# Tesla.net
KiCad netlist of a schematic drawn in EAGLE
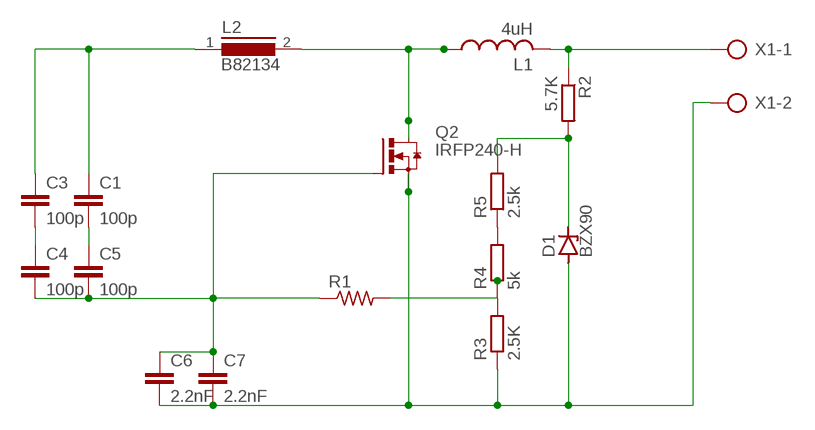
[diagram p0: schematic, sheet 1]

(export (version "E")
  (design (tool "Eeschema 10.0.6"))
  (components
    (comp (ref "C1")
      (value "100p")
      (footprint "eagle-import:C15B5")
      (libsource (lib "eagle-import") (part "C15/5"))
    )
    (comp (ref "C3")
      (value "100p")
      (footprint "eagle-import:C15B5")
      (libsource (lib "eagle-import") (part "C15/5"))
    )
    (comp (ref "C4")
      (value "100p")
      (footprint "eagle-import:C15B5")
      (libsource (lib "eagle-import") (part "C15/5"))
    )
    (comp (ref "C5")
      (value "100p")
      (footprint "eagle-import:C15B5")
      (libsource (lib "eagle-import") (part "C15/5"))
    )
    (comp (ref "C6")
      (value "2.2nF")
      (footprint "eagle-import:C15B5")
      (libsource (lib "eagle-import") (part "C15/5"))
    )
    (comp (ref "C7")
      (value "2.2nF")
      (footprint "eagle-import:C15B5")
      (libsource (lib "eagle-import") (part "C15/5"))
    )
    (comp (ref "D1")
      (value "BZX90")
      (footprint "eagle-import:DO34Z7")
      (libsource (lib "eagle-import") (part "BZX90"))
    )
    (comp (ref "L1")
      (value "4uH")
      (footprint "eagle-import:TFI0510")
      (libsource (lib "eagle-import") (part "L-USTFI0510"))
    )
    (comp (ref "L2")
      (value "B82134")
      (footprint "eagle-import:SUKW4-32")
      (libsource (lib "eagle-import") (part "B82134"))
    )
    (comp (ref "Q2")
      (value "IRFP240-H")
      (footprint "eagle-import:TO247BH")
      (libsource (lib "eagle-import") (part "IRFP240-H"))
    )
    (comp (ref "R1")
      (value "R-US_0309/12")
      (footprint "eagle-import:0309_12")
      (libsource (lib "eagle-import") (part "R-US_0309/12"))
    )
    (comp (ref "R2")
      (value "5.7K")
      (footprint "eagle-import:0204_7")
      (libsource (lib "eagle-import") (part "R-EU_0204/7"))
    )
    (comp (ref "R3")
      (value "2.5K")
      (footprint "eagle-import:0204_7")
      (libsource (lib "eagle-import") (part "R-EU_0204/7"))
    )
    (comp (ref "R4")
      (value "5k")
      (footprint "eagle-import:0204_7")
      (libsource (lib "eagle-import") (part "R-EU_0204/7"))
    )
    (comp (ref "R5")
      (value "2.5k")
      (footprint "eagle-import:0204_7")
      (libsource (lib "eagle-import") (part "R-EU_0204/7"))
    )
    (comp (ref "X1")
      (value "AK300/2")
      (footprint "eagle-import:AK300_2")
      (libsource (lib "eagle-import") (part "AK300/2"))
    )
  )
  (nets
    (net (code "1") (name "Net-(C1-Pad1)") (class "Default")
      (node (ref "C1") (pin "1") (pinfunction "1_1") (pintype "passive"))
      (node (ref "C3") (pin "1") (pinfunction "1_1") (pintype "passive"))
      (node (ref "L2") (pin "1") (pinfunction "1_1") (pintype "passive"))
    )
    (net (code "2") (name "Net-(C1-Pad2)") (class "Default")
      (node (ref "C1") (pin "2") (pinfunction "2_2") (pintype "passive"))
      (node (ref "C5") (pin "1") (pinfunction "1_1") (pintype "passive"))
    )
    (net (code "3") (name "Net-(C3-Pad2)") (class "Default")
      (node (ref "C3") (pin "2") (pinfunction "2_2") (pintype "passive"))
      (node (ref "C4") (pin "1") (pinfunction "1_1") (pintype "passive"))
    )
    (net (code "4") (name "Net-(C4-Pad2)") (class "Default")
      (node (ref "C4") (pin "2") (pinfunction "2_2") (pintype "passive"))
      (node (ref "C5") (pin "2") (pinfunction "2_2") (pintype "passive"))
      (node (ref "C6") (pin "1") (pinfunction "1_1") (pintype "passive"))
      (node (ref "C7") (pin "1") (pinfunction "1_1") (pintype "passive"))
      (node (ref "Q2") (pin "G") (pinfunction "G_G") (pintype "passive"))
      (node (ref "R1") (pin "1") (pinfunction "1_1") (pintype "passive"))
    )
    (net (code "5") (name "Net-(D1-PadC)") (class "Default")
      (node (ref "D1") (pin "C") (pinfunction "C_C") (pintype "passive"))
      (node (ref "R2") (pin "2") (pinfunction "2_2") (pintype "passive"))
      (node (ref "R5") (pin "2") (pinfunction "2_2") (pintype "passive"))
    )
    (net (code "6") (name "Net-(L1-Pad1)") (class "Default")
      (node (ref "L1") (pin "1") (pinfunction "1_1") (pintype "passive"))
      (node (ref "L2") (pin "2") (pinfunction "2_2") (pintype "passive"))
      (node (ref "Q2") (pin "D") (pinfunction "D_D") (pintype "passive"))
    )
    (net (code "7") (name "Net-(R1-Pad2)") (class "Default")
      (node (ref "R1") (pin "2") (pinfunction "2_2") (pintype "passive"))
      (node (ref "R3") (pin "2") (pinfunction "2_2") (pintype "passive"))
      (node (ref "R4") (pin "1") (pinfunction "1_1") (pintype "passive"))
    )
    (net (code "8") (name "Net-(R4-Pad2)") (class "Default")
      (node (ref "R4") (pin "2") (pinfunction "2_2") (pintype "passive"))
      (node (ref "R5") (pin "1") (pinfunction "1_1") (pintype "passive"))
    )
    (net (code "9") (name "Net-(X1A-KL)") (class "Default")
      (node (ref "L1") (pin "2") (pinfunction "2_2") (pintype "passive"))
      (node (ref "R2") (pin "1") (pinfunction "1_1") (pintype "passive"))
      (node (ref "X1") (pin "1") (pinfunction "KL_1") (pintype "passive"))
    )
    (net (code "10") (name "Net-(X1B-KL)") (class "Default")
      (node (ref "C6") (pin "2") (pinfunction "2_2") (pintype "passive"))
      (node (ref "C7") (pin "2") (pinfunction "2_2") (pintype "passive"))
      (node (ref "D1") (pin "A") (pinfunction "A_A") (pintype "passive"))
      (node (ref "Q2") (pin "S") (pinfunction "S_S") (pintype "passive"))
      (node (ref "R3") (pin "1") (pinfunction "1_1") (pintype "passive"))
      (node (ref "X1") (pin "2") (pinfunction "KL_2") (pintype "passive"))
    )
  )
)
